# rtm-top.net
KiCad netlist of a schematic drawn in Altium Designer
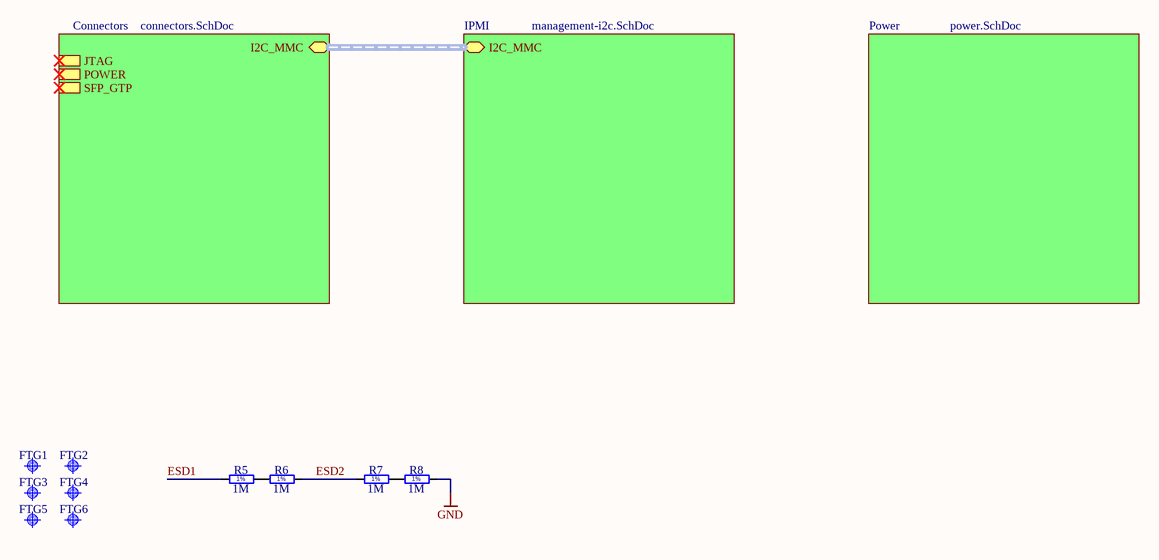
[diagram p0: rtm-top.SchDoc]

(export (version "E")
  (design (tool "Eeschema 10.0.6"))
  (components
    (comp (ref "FTG1")
      (value "Use only in PCB")
      (footprint "FIDUCIAL_TOP_C100-200")
      (description "Fiducial Target")
      (fields (field (name "PART NUMBER") "FIDUCIAL_TARGET_C100-200") (field (name "AUTHOR") "CERN DEM JLC"))
      (libsource (lib "Eletro-mechanical") (part "Fiducial Target"))
    )
    (comp (ref "FTG2")
      (value "Use only in PCB")
      (footprint "FIDUCIAL_TOP_C100-200")
      (description "Fiducial Target")
      (fields (field (name "PART NUMBER") "FIDUCIAL_TARGET_C100-200") (field (name "AUTHOR") "CERN DEM JLC"))
      (libsource (lib "Eletro-mechanical") (part "Fiducial Target"))
    )
    (comp (ref "FTG3")
      (value "Use only in PCB")
      (footprint "FIDUCIAL_TOP_C100-200")
      (description "Fiducial Target")
      (fields (field (name "PART NUMBER") "FIDUCIAL_TARGET_C100-200") (field (name "AUTHOR") "CERN DEM JLC"))
      (libsource (lib "Eletro-mechanical") (part "Fiducial Target"))
    )
    (comp (ref "FTG4")
      (value "Use only in PCB")
      (footprint "FIDUCIAL_TOP_C100-200")
      (description "Fiducial Target")
      (fields (field (name "PART NUMBER") "FIDUCIAL_TARGET_C100-200") (field (name "AUTHOR") "CERN DEM JLC"))
      (libsource (lib "Eletro-mechanical") (part "Fiducial Target"))
    )
    (comp (ref "FTG5")
      (value "Use only in PCB")
      (footprint "FIDUCIAL_TOP_C100-200")
      (description "Fiducial Target")
      (fields (field (name "PART NUMBER") "FIDUCIAL_TARGET_C100-200") (field (name "AUTHOR") "CERN DEM JLC"))
      (libsource (lib "Eletro-mechanical") (part "Fiducial Target"))
    )
    (comp (ref "FTG6")
      (value "Use only in PCB")
      (footprint "FIDUCIAL_TOP_C100-200")
      (description "Fiducial Target")
      (fields (field (name "PART NUMBER") "FIDUCIAL_TARGET_C100-200") (field (name "AUTHOR") "CERN DEM JLC"))
      (libsource (lib "Eletro-mechanical") (part "Fiducial Target"))
    )
    (comp (ref "R5")
      (value "1M")
      (footprint "RESC3216X65N")
      (description "Resistor - 1%")
      (fields
        (field (name "PART NUMBER") "R1206_1M_1%_0.25W_100PPM")
        (field (name "POWER") "0.25W")
        (field (name "AUTHOR") "CERN DEM JLC")
      )
      (libsource (lib "Resistors") (part "Resistor - 1%"))
    )
    (comp (ref "R6")
      (value "1M")
      (footprint "RESC3216X65N")
      (description "Resistor - 1%")
      (fields
        (field (name "PART NUMBER") "R1206_1M_1%_0.25W_100PPM")
        (field (name "POWER") "0.25W")
        (field (name "AUTHOR") "CERN DEM JLC")
      )
      (libsource (lib "Resistors") (part "Resistor - 1%"))
    )
    (comp (ref "R7")
      (value "1M")
      (footprint "RESC3216X65N")
      (description "Resistor - 1%")
      (fields
        (field (name "PART NUMBER") "R1206_1M_1%_0.25W_100PPM")
        (field (name "POWER") "0.25W")
        (field (name "AUTHOR") "CERN DEM JLC")
      )
      (libsource (lib "Resistors") (part "Resistor - 1%"))
    )
    (comp (ref "R8")
      (value "1M")
      (footprint "RESC3216X65N")
      (description "Resistor - 1%")
      (fields
        (field (name "PART NUMBER") "R1206_1M_1%_0.25W_100PPM")
        (field (name "POWER") "0.25W")
        (field (name "AUTHOR") "CERN DEM JLC")
      )
      (libsource (lib "Resistors") (part "Resistor - 1%"))
    )
  )
  (nets
    (net (code "1") (name "/ESD1") (class "Default")
      (node (ref "R5") (pin "1") (pinfunction "1_1") (pintype "passive"))
    )
    (net (code "2") (name "/ESD2") (class "Default")
      (node (ref "R6") (pin "2") (pinfunction "2_2") (pintype "passive"))
      (node (ref "R7") (pin "1") (pinfunction "1_1") (pintype "passive"))
    )
    (net (code "7") (name "GND") (class "Default")
      (node (ref "R8") (pin "2") (pinfunction "2_2") (pintype "passive"))
    )
    (net (code "8") (name "Net-(R5-Pad2)") (class "Default")
      (node (ref "R5") (pin "2") (pinfunction "2_2") (pintype "passive"))
      (node (ref "R6") (pin "1") (pinfunction "1_1") (pintype "passive"))
    )
    (net (code "9") (name "Net-(R7-Pad2)") (class "Default")
      (node (ref "R7") (pin "2") (pinfunction "2_2") (pintype "passive"))
      (node (ref "R8") (pin "1") (pinfunction "1_1") (pintype "passive"))
    )
  )
)
